# LTM8056.net
KiCad netlist of a schematic drawn in Altium Designer
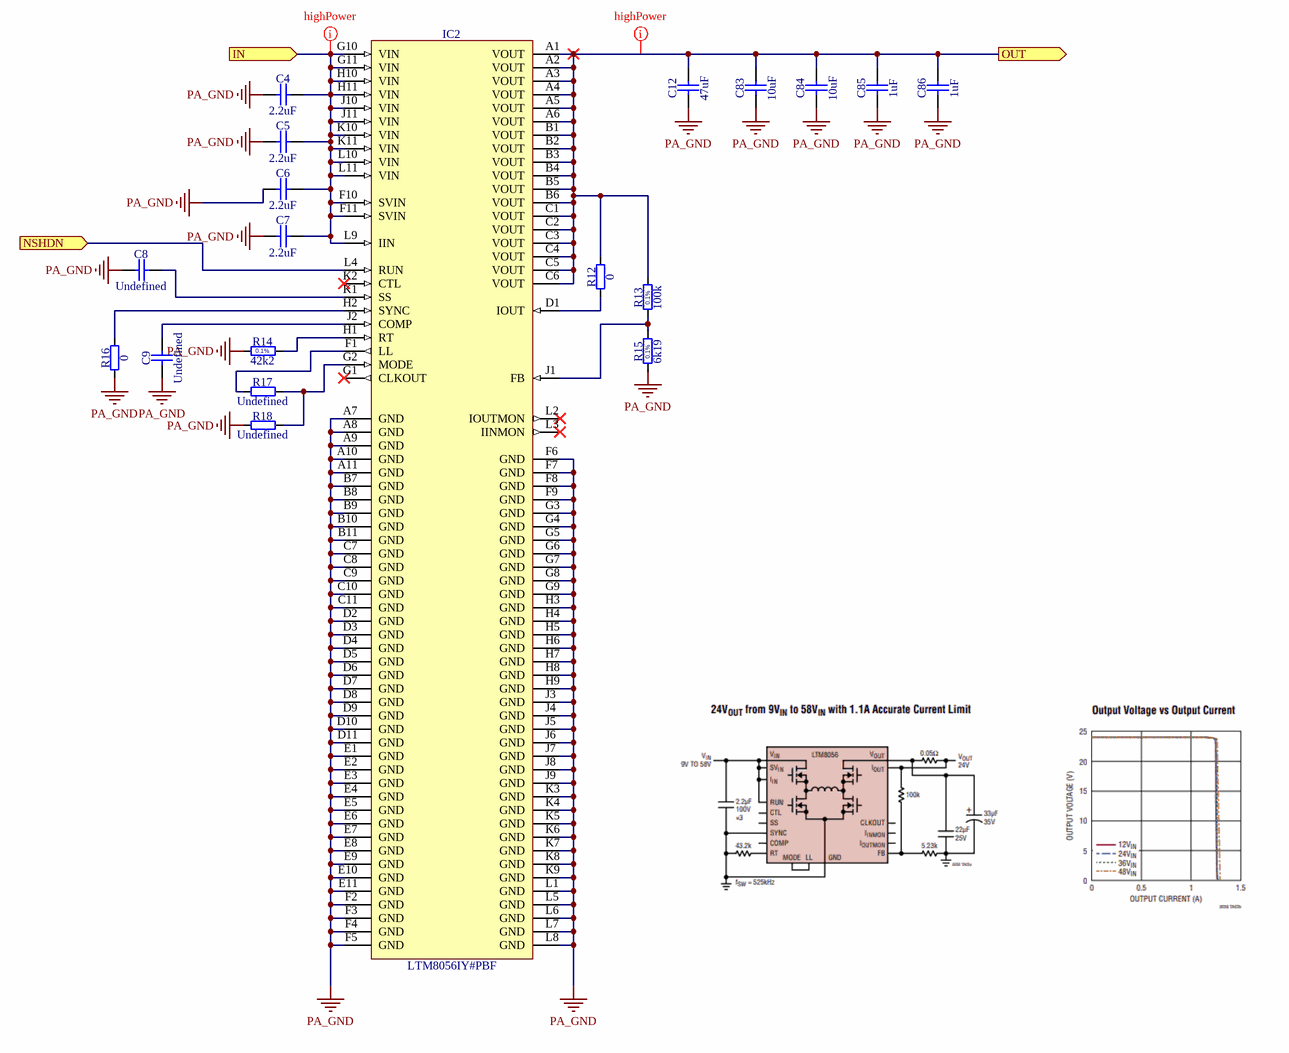
[diagram p0: LTM8056.SchDoc]

(export (version "E")
  (design (tool "Eeschema 10.0.6"))
  (components
    (comp (ref "C4")
      (value "2.2uF")
      (footprint "CAPC3216X180N")
      (description "Non-polarised capacitor")
      (fields
        (field (name "PART NUMBER") "CC1206_2.2UF_50V_10%_X7R")
        (field (name "VOLTAGE") "50V")
        (field (name "AUTHOR") "CERN DEM MR")
      )
      (libsource (lib "Capacitors") (part "Capacitor - non polarized"))
    )
    (comp (ref "C5")
      (value "2.2uF")
      (footprint "CAPC3216X180N")
      (description "Non-polarised capacitor")
      (fields
        (field (name "PART NUMBER") "CC1206_2.2UF_50V_10%_X7R")
        (field (name "VOLTAGE") "50V")
        (field (name "AUTHOR") "CERN DEM MR")
      )
      (libsource (lib "Capacitors") (part "Capacitor - non polarized"))
    )
    (comp (ref "C6")
      (value "2.2uF")
      (footprint "CAPC3216X180N")
      (description "Non-polarised capacitor")
      (fields
        (field (name "PART NUMBER") "CC1206_2.2UF_50V_10%_X7R")
        (field (name "VOLTAGE") "50V")
        (field (name "AUTHOR") "CERN DEM MR")
      )
      (libsource (lib "Capacitors") (part "Capacitor - non polarized"))
    )
    (comp (ref "C7")
      (value "2.2uF")
      (footprint "CAPC3216X180N")
      (description "Non-polarised capacitor")
      (fields
        (field (name "PART NUMBER") "CC1206_2.2UF_50V_10%_X7R")
        (field (name "VOLTAGE") "50V")
        (field (name "AUTHOR") "CERN DEM MR")
      )
      (libsource (lib "Capacitors") (part "Capacitor - non polarized"))
    )
    (comp (ref "C8")
      (value "Undefined")
      (footprint "CAPC1608X90N")
      (description "Non-polarised capacitor")
      (fields (field (name "PART NUMBER") "CC0603_NO-VALUE") (field (name "AUTHOR") "CERN DEM MR"))
      (libsource (lib "Capacitors") (part "Capacitor - non polarized"))
    )
    (comp (ref "C9")
      (value "Undefined")
      (footprint "CAPC1608X90N")
      (description "Non-polarised capacitor")
      (fields (field (name "PART NUMBER") "CC0603_NO-VALUE") (field (name "AUTHOR") "CERN DEM MR"))
      (libsource (lib "Capacitors") (part "Capacitor - non polarized"))
    )
    (comp (ref "C12")
      (value "47uF")
      (footprint "CAPC_TDK_CKG57N")
      (description "Non-polarised capacitor")
      (fields
        (field (name "PART NUMBER") "CC2220_47UF_25V_20%_X7S_TDK_CKG57N")
        (field (name "VOLTAGE") "25V")
        (field (name "AUTHOR") "CERN DEM JLC")
      )
      (libsource (lib "Capacitors") (part "Capacitor - non polarized"))
    )
    (comp (ref "C83")
      (value "10uF")
      (footprint "CAPC3225X280N")
      (description "Non-polarised capacitor")
      (fields
        (field (name "PART NUMBER") "CC1210_10UF_50V_10%_X7R_YUDEN_UMK325AB7106KMHP")
        (field (name "VOLTAGE") "50V")
        (field (name "AUTHOR") "CERN DEM JLC")
      )
      (libsource (lib "Capacitors") (part "Capacitor - non polarized"))
    )
    (comp (ref "C84")
      (value "10uF")
      (footprint "CAPC3225X280N")
      (description "Non-polarised capacitor")
      (fields
        (field (name "PART NUMBER") "CC1210_10UF_50V_10%_X7R_YUDEN_UMK325AB7106KMHP")
        (field (name "VOLTAGE") "50V")
        (field (name "AUTHOR") "CERN DEM JLC")
      )
      (libsource (lib "Capacitors") (part "Capacitor - non polarized"))
    )
    (comp (ref "C85")
      (value "1uF")
      (footprint "CAPC1608X87N")
      (description "Non-polarised capacitor")
      (fields
        (field (name "PART NUMBER") "CC0603_1UF_50V_10%_X5R")
        (field (name "VOLTAGE") "50V")
        (field (name "AUTHOR") "CERN DEM JMW")
      )
      (libsource (lib "Capacitors") (part "Capacitor - non polarized"))
    )
    (comp (ref "C86")
      (value "1uF")
      (footprint "CAPC1608X87N")
      (description "Non-polarised capacitor")
      (fields
        (field (name "PART NUMBER") "CC0603_1UF_50V_10%_X5R")
        (field (name "VOLTAGE") "50V")
        (field (name "AUTHOR") "CERN DEM JMW")
      )
      (libsource (lib "Capacitors") (part "Capacitor - non polarized"))
    )
    (comp (ref "IC2")
      (value "LTM8056IY#PBF")
      (footprint "BGA121C127P11X11_1500X1500X512")
      (description "58VIN, 48VOUT Buck-Boost µModule Regulator")
      (fields (field (name "MANUFACTURER") "LINEAR TECHNOLOGY") (field (name "AUTHOR") "CERN DEM JLC"))
      (libsource (lib "ICs And Semiconductors") (part "LTM8056"))
    )
    (comp (ref "R12")
      (value "0")
      (footprint "RESC1608X55N")
      (description "Resistor")
      (fields
        (field (name "PART NUMBER") "R0603_0R_JUMPER")
        (field (name "MANUFACTURER") "GENERIC")
        (field (name "AUTHOR") "CERN DEM JLC")
      )
      (libsource (lib "Resistors") (part "Resistor"))
    )
    (comp (ref "R13")
      (value "100k")
      (footprint "RESC1608X55N")
      (description "Resistor - 0.1%")
      (fields
        (field (name "PART NUMBER") "R0603_100K_0.1%_0.063W_10PPM")
        (field (name "POWER") "0.063W")
        (field (name "AUTHOR") "CERN DEM JLC")
      )
      (libsource (lib "Resistors") (part "Resistor - 0.1%"))
    )
    (comp (ref "R14")
      (value "42k2")
      (footprint "RESC1608X55N")
      (description "Resistor - 0.1%")
      (fields
        (field (name "PART NUMBER") "R0603_42K2_0.1%_0.063W_10PPM")
        (field (name "POWER") "0.063W")
        (field (name "AUTHOR") "CERN DEM JLC")
      )
      (libsource (lib "Resistors") (part "Resistor - 0.1%"))
    )
    (comp (ref "R15")
      (value "6k19")
      (footprint "RESC1608X55N")
      (description "Resistor - 0.1%")
      (fields
        (field (name "PART NUMBER") "R0603_6K19_0.1%_0.063W_10PPM")
        (field (name "POWER") "0.063W")
        (field (name "AUTHOR") "CERN DEM JLC")
      )
      (libsource (lib "Resistors") (part "Resistor - 0.1%"))
    )
    (comp (ref "R16")
      (value "0")
      (footprint "RESC1608X55N")
      (description "Resistor")
      (fields
        (field (name "PART NUMBER") "R0603_0R_JUMPER")
        (field (name "MANUFACTURER") "GENERIC")
        (field (name "AUTHOR") "CERN DEM JLC")
      )
      (libsource (lib "Resistors") (part "Resistor"))
    )
    (comp (ref "R17")
      (value "Undefined")
      (footprint "RESC1608X55N")
      (description "Resistor")
      (fields (field (name "PART NUMBER") "R0603_NO-VALUE") (field (name "AUTHOR") "CERN DEM JLC"))
      (libsource (lib "Resistors") (part "Resistor"))
    )
    (comp (ref "R18")
      (value "Undefined")
      (footprint "RESC1608X55N")
      (description "Resistor")
      (fields (field (name "PART NUMBER") "R0603_NO-VALUE") (field (name "AUTHOR") "CERN DEM JLC"))
      (libsource (lib "Resistors") (part "Resistor"))
    )
  )
  (nets
    (net (code "1") (name "/IN") (class "Default")
      (node (ref "C4") (pin "2") (pinfunction "2_2") (pintype "passive"))
      (node (ref "C5") (pin "2") (pinfunction "2_2") (pintype "passive"))
      (node (ref "C6") (pin "2") (pinfunction "2_2") (pintype "passive"))
      (node (ref "C7") (pin "2") (pinfunction "2_2") (pintype "passive"))
      (node (ref "IC2") (pin "F10") (pinfunction "SVIN_F10") (pintype "input"))
      (node (ref "IC2") (pin "F11") (pinfunction "SVIN_F11") (pintype "input"))
      (node (ref "IC2") (pin "G10") (pinfunction "VIN_G10") (pintype "input"))
      (node (ref "IC2") (pin "G11") (pinfunction "VIN_G11") (pintype "input"))
      (node (ref "IC2") (pin "H10") (pinfunction "VIN_H10") (pintype "input"))
      (node (ref "IC2") (pin "H11") (pinfunction "VIN_H11") (pintype "input"))
      (node (ref "IC2") (pin "J10") (pinfunction "VIN_J10") (pintype "input"))
      (node (ref "IC2") (pin "J11") (pinfunction "VIN_J11") (pintype "input"))
      (node (ref "IC2") (pin "K10") (pinfunction "VIN_K10") (pintype "input"))
      (node (ref "IC2") (pin "K11") (pinfunction "VIN_K11") (pintype "input"))
      (node (ref "IC2") (pin "L10") (pinfunction "VIN_L10") (pintype "input"))
      (node (ref "IC2") (pin "L11") (pinfunction "VIN_L11") (pintype "input"))
      (node (ref "IC2") (pin "L9") (pinfunction "IIN_L9") (pintype "input"))
    )
    (net (code "2") (name "/NSHDN") (class "Default")
      (node (ref "IC2") (pin "L4") (pinfunction "RUN_L4") (pintype "input"))
    )
    (net (code "3") (name "/OUT") (class "Default")
      (node (ref "C12") (pin "2") (pinfunction "2_2") (pintype "passive"))
      (node (ref "C83") (pin "2") (pinfunction "2_2") (pintype "passive"))
      (node (ref "C84") (pin "2") (pinfunction "2_2") (pintype "passive"))
      (node (ref "C85") (pin "2") (pinfunction "2_2") (pintype "passive"))
      (node (ref "C86") (pin "2") (pinfunction "2_2") (pintype "passive"))
      (node (ref "IC2") (pin "A1") (pinfunction "VOUT_A1") (pintype "power_in"))
      (node (ref "IC2") (pin "A2") (pinfunction "VOUT_A2") (pintype "power_in"))
      (node (ref "IC2") (pin "A3") (pinfunction "VOUT_A3") (pintype "power_in"))
      (node (ref "IC2") (pin "A4") (pinfunction "VOUT_A4") (pintype "power_in"))
      (node (ref "IC2") (pin "A5") (pinfunction "VOUT_A5") (pintype "power_in"))
      (node (ref "IC2") (pin "A6") (pinfunction "VOUT_A6") (pintype "power_in"))
      (node (ref "IC2") (pin "B1") (pinfunction "VOUT_B1") (pintype "power_in"))
      (node (ref "IC2") (pin "B2") (pinfunction "VOUT_B2") (pintype "power_in"))
      (node (ref "IC2") (pin "B3") (pinfunction "VOUT_B3") (pintype "power_in"))
      (node (ref "IC2") (pin "B4") (pinfunction "VOUT_B4") (pintype "power_in"))
      (node (ref "IC2") (pin "B5") (pinfunction "VOUT_B5") (pintype "power_in"))
      (node (ref "IC2") (pin "B6") (pinfunction "VOUT_B6") (pintype "power_in"))
      (node (ref "IC2") (pin "C1") (pinfunction "VOUT_C1") (pintype "power_in"))
      (node (ref "IC2") (pin "C2") (pinfunction "VOUT_C2") (pintype "power_in"))
      (node (ref "IC2") (pin "C3") (pinfunction "VOUT_C3") (pintype "power_in"))
      (node (ref "IC2") (pin "C4") (pinfunction "VOUT_C4") (pintype "power_in"))
      (node (ref "IC2") (pin "C5") (pinfunction "VOUT_C5") (pintype "power_in"))
      (node (ref "IC2") (pin "C6") (pinfunction "VOUT_C6") (pintype "power_in"))
      (node (ref "R12") (pin "2") (pinfunction "2_2") (pintype "passive"))
      (node (ref "R13") (pin "2") (pinfunction "2_2") (pintype "passive"))
    )
    (net (code "4") (name "Net-(IC2-COMP)") (class "Default")
      (node (ref "C9") (pin "2") (pinfunction "2_2") (pintype "passive"))
      (node (ref "IC2") (pin "J2") (pinfunction "COMP_J2") (pintype "input"))
    )
    (net (code "5") (name "Net-(IC2-FB)") (class "Default")
      (node (ref "IC2") (pin "J1") (pinfunction "FB_J1") (pintype "input"))
      (node (ref "R13") (pin "1") (pinfunction "1_1") (pintype "passive"))
      (node (ref "R15") (pin "2") (pinfunction "2_2") (pintype "passive"))
    )
    (net (code "6") (name "Net-(IC2-IOUT)") (class "Default")
      (node (ref "IC2") (pin "D1") (pinfunction "IOUT_D1") (pintype "input"))
      (node (ref "R12") (pin "1") (pinfunction "1_1") (pintype "passive"))
    )
    (net (code "7") (name "Net-(IC2-LL)") (class "Default")
      (node (ref "IC2") (pin "F1") (pinfunction "LL_F1") (pintype "output"))
      (node (ref "R17") (pin "1") (pinfunction "1_1") (pintype "passive"))
    )
    (net (code "8") (name "Net-(IC2-MODE)") (class "Default")
      (node (ref "IC2") (pin "G2") (pinfunction "MODE_G2") (pintype "input"))
      (node (ref "R17") (pin "2") (pinfunction "2_2") (pintype "passive"))
      (node (ref "R18") (pin "2") (pinfunction "2_2") (pintype "passive"))
    )
    (net (code "9") (name "Net-(IC2-RT)") (class "Default")
      (node (ref "IC2") (pin "H1") (pinfunction "RT_H1") (pintype "input"))
      (node (ref "R14") (pin "2") (pinfunction "2_2") (pintype "passive"))
    )
    (net (code "10") (name "Net-(IC2-SS)") (class "Default")
      (node (ref "C8") (pin "2") (pinfunction "2_2") (pintype "passive"))
      (node (ref "IC2") (pin "K1") (pinfunction "SS_K1") (pintype "input"))
    )
    (net (code "11") (name "Net-(IC2-SYNC)") (class "Default")
      (node (ref "IC2") (pin "H2") (pinfunction "SYNC_H2") (pintype "input"))
      (node (ref "R16") (pin "2") (pinfunction "2_2") (pintype "passive"))
    )
    (net (code "12") (name "PA_GND") (class "Default")
      (node (ref "C12") (pin "1") (pinfunction "1_1") (pintype "passive"))
      (node (ref "C4") (pin "1") (pinfunction "1_1") (pintype "passive"))
      (node (ref "C5") (pin "1") (pinfunction "1_1") (pintype "passive"))
      (node (ref "C6") (pin "1") (pinfunction "1_1") (pintype "passive"))
      (node (ref "C7") (pin "1") (pinfunction "1_1") (pintype "passive"))
      (node (ref "C8") (pin "1") (pinfunction "1_1") (pintype "passive"))
      (node (ref "C83") (pin "1") (pinfunction "1_1") (pintype "passive"))
      (node (ref "C84") (pin "1") (pinfunction "1_1") (pintype "passive"))
      (node (ref "C85") (pin "1") (pinfunction "1_1") (pintype "passive"))
      (node (ref "C86") (pin "1") (pinfunction "1_1") (pintype "passive"))
      (node (ref "C9") (pin "1") (pinfunction "1_1") (pintype "passive"))
      (node (ref "IC2") (pin "A10") (pinfunction "GND_A10") (pintype "power_in"))
      (node (ref "IC2") (pin "A11") (pinfunction "GND_A11") (pintype "power_in"))
      (node (ref "IC2") (pin "A7") (pinfunction "GND_A7") (pintype "power_in"))
      (node (ref "IC2") (pin "A8") (pinfunction "GND_A8") (pintype "power_in"))
      (node (ref "IC2") (pin "A9") (pinfunction "GND_A9") (pintype "power_in"))
      (node (ref "IC2") (pin "B10") (pinfunction "GND_B10") (pintype "power_in"))
      (node (ref "IC2") (pin "B11") (pinfunction "GND_B11") (pintype "power_in"))
      (node (ref "IC2") (pin "B7") (pinfunction "GND_B7") (pintype "power_in"))
      (node (ref "IC2") (pin "B8") (pinfunction "GND_B8") (pintype "power_in"))
      (node (ref "IC2") (pin "B9") (pinfunction "GND_B9") (pintype "power_in"))
      (node (ref "IC2") (pin "C10") (pinfunction "GND_C10") (pintype "power_in"))
      (node (ref "IC2") (pin "C11") (pinfunction "GND_C11") (pintype "power_in"))
      (node (ref "IC2") (pin "C7") (pinfunction "GND_C7") (pintype "power_in"))
      (node (ref "IC2") (pin "C8") (pinfunction "GND_C8") (pintype "power_in"))
      (node (ref "IC2") (pin "C9") (pinfunction "GND_C9") (pintype "power_in"))
      (node (ref "IC2") (pin "D10") (pinfunction "GND_D10") (pintype "power_in"))
      (node (ref "IC2") (pin "D11") (pinfunction "GND_D11") (pintype "power_in"))
      (node (ref "IC2") (pin "D2") (pinfunction "GND_D2") (pintype "power_in"))
      (node (ref "IC2") (pin "D3") (pinfunction "GND_D3") (pintype "power_in"))
      (node (ref "IC2") (pin "D4") (pinfunction "GND_D4") (pintype "power_in"))
      (node (ref "IC2") (pin "D5") (pinfunction "GND_D5") (pintype "power_in"))
      (node (ref "IC2") (pin "D6") (pinfunction "GND_D6") (pintype "power_in"))
      (node (ref "IC2") (pin "D7") (pinfunction "GND_D7") (pintype "power_in"))
      (node (ref "IC2") (pin "D8") (pinfunction "GND_D8") (pintype "power_in"))
      (node (ref "IC2") (pin "D9") (pinfunction "GND_D9") (pintype "power_in"))
      (node (ref "IC2") (pin "E1") (pinfunction "GND_E1") (pintype "power_in"))
      (node (ref "IC2") (pin "E10") (pinfunction "GND_E10") (pintype "power_in"))
      (node (ref "IC2") (pin "E11") (pinfunction "GND_E11") (pintype "power_in"))
      (node (ref "IC2") (pin "E2") (pinfunction "GND_E2") (pintype "power_in"))
      (node (ref "IC2") (pin "E3") (pinfunction "GND_E3") (pintype "power_in"))
      (node (ref "IC2") (pin "E4") (pinfunction "GND_E4") (pintype "power_in"))
      (node (ref "IC2") (pin "E5") (pinfunction "GND_E5") (pintype "power_in"))
      (node (ref "IC2") (pin "E6") (pinfunction "GND_E6") (pintype "power_in"))
      (node (ref "IC2") (pin "E7") (pinfunction "GND_E7") (pintype "power_in"))
      (node (ref "IC2") (pin "E8") (pinfunction "GND_E8") (pintype "power_in"))
      (node (ref "IC2") (pin "E9") (pinfunction "GND_E9") (pintype "power_in"))
      (node (ref "IC2") (pin "F2") (pinfunction "GND_F2") (pintype "power_in"))
      (node (ref "IC2") (pin "F3") (pinfunction "GND_F3") (pintype "power_in"))
      (node (ref "IC2") (pin "F4") (pinfunction "GND_F4") (pintype "power_in"))
      (node (ref "IC2") (pin "F5") (pinfunction "GND_F5") (pintype "power_in"))
      (node (ref "IC2") (pin "F6") (pinfunction "GND_F6") (pintype "power_in"))
      (node (ref "IC2") (pin "F7") (pinfunction "GND_F7") (pintype "power_in"))
      (node (ref "IC2") (pin "F8") (pinfunction "GND_F8") (pintype "power_in"))
      (node (ref "IC2") (pin "F9") (pinfunction "GND_F9") (pintype "power_in"))
      (node (ref "IC2") (pin "G3") (pinfunction "GND_G3") (pintype "power_in"))
      (node (ref "IC2") (pin "G4") (pinfunction "GND_G4") (pintype "power_in"))
      (node (ref "IC2") (pin "G5") (pinfunction "GND_G5") (pintype "power_in"))
      (node (ref "IC2") (pin "G6") (pinfunction "GND_G6") (pintype "power_in"))
      (node (ref "IC2") (pin "G7") (pinfunction "GND_G7") (pintype "power_in"))
      (node (ref "IC2") (pin "G8") (pinfunction "GND_G8") (pintype "power_in"))
      (node (ref "IC2") (pin "G9") (pinfunction "GND_G9") (pintype "power_in"))
      (node (ref "IC2") (pin "H3") (pinfunction "GND_H3") (pintype "power_in"))
      (node (ref "IC2") (pin "H4") (pinfunction "GND_H4") (pintype "power_in"))
      (node (ref "IC2") (pin "H5") (pinfunction "GND_H5") (pintype "power_in"))
      (node (ref "IC2") (pin "H6") (pinfunction "GND_H6") (pintype "power_in"))
      (node (ref "IC2") (pin "H7") (pinfunction "GND_H7") (pintype "power_in"))
      (node (ref "IC2") (pin "H8") (pinfunction "GND_H8") (pintype "power_in"))
      (node (ref "IC2") (pin "H9") (pinfunction "GND_H9") (pintype "power_in"))
      (node (ref "IC2") (pin "J3") (pinfunction "GND_J3") (pintype "power_in"))
      (node (ref "IC2") (pin "J4") (pinfunction "GND_J4") (pintype "power_in"))
      (node (ref "IC2") (pin "J5") (pinfunction "GND_J5") (pintype "power_in"))
      (node (ref "IC2") (pin "J6") (pinfunction "GND_J6") (pintype "power_in"))
      (node (ref "IC2") (pin "J7") (pinfunction "GND_J7") (pintype "power_in"))
      (node (ref "IC2") (pin "J8") (pinfunction "GND_J8") (pintype "power_in"))
      (node (ref "IC2") (pin "J9") (pinfunction "GND_J9") (pintype "power_in"))
      (node (ref "IC2") (pin "K3") (pinfunction "GND_K3") (pintype "power_in"))
      (node (ref "IC2") (pin "K4") (pinfunction "GND_K4") (pintype "power_in"))
      (node (ref "IC2") (pin "K5") (pinfunction "GND_K5") (pintype "power_in"))
      (node (ref "IC2") (pin "K6") (pinfunction "GND_K6") (pintype "power_in"))
      (node (ref "IC2") (pin "K7") (pinfunction "GND_K7") (pintype "power_in"))
      (node (ref "IC2") (pin "K8") (pinfunction "GND_K8") (pintype "power_in"))
      (node (ref "IC2") (pin "K9") (pinfunction "GND_K9") (pintype "power_in"))
      (node (ref "IC2") (pin "L1") (pinfunction "GND_L1") (pintype "power_in"))
      (node (ref "IC2") (pin "L5") (pinfunction "GND_L5") (pintype "power_in"))
      (node (ref "IC2") (pin "L6") (pinfunction "GND_L6") (pintype "power_in"))
      (node (ref "IC2") (pin "L7") (pinfunction "GND_L7") (pintype "power_in"))
      (node (ref "IC2") (pin "L8") (pinfunction "GND_L8") (pintype "power_in"))
      (node (ref "R14") (pin "1") (pinfunction "1_1") (pintype "passive"))
      (node (ref "R15") (pin "1") (pinfunction "1_1") (pintype "passive"))
      (node (ref "R16") (pin "1") (pinfunction "1_1") (pintype "passive"))
      (node (ref "R18") (pin "1") (pinfunction "1_1") (pintype "passive"))
    )
    (net (code "13") (name "unconnected-(IC2-CLKOUT-PadG1)") (class "Default")
      (node (ref "IC2") (pin "G1") (pinfunction "CLKOUT_G1") (pintype "output+no_connect"))
    )
    (net (code "14") (name "unconnected-(IC2-CTL-PadK2)") (class "Default")
      (node (ref "IC2") (pin "K2") (pinfunction "CTL_K2") (pintype "input+no_connect"))
    )
    (net (code "15") (name "unconnected-(IC2-IINMON-PadL3)") (class "Default")
      (node (ref "IC2") (pin "L3") (pinfunction "IINMON_L3") (pintype "output+no_connect"))
    )
    (net (code "16") (name "unconnected-(IC2-IOUTMON-PadL2)") (class "Default")
      (node (ref "IC2") (pin "L2") (pinfunction "IOUTMON_L2") (pintype "output+no_connect"))
    )
  )
)
